# SCH_Custom_Arduino_2022-07-22.net
KiCad netlist of a schematic drawn in EasyEDA
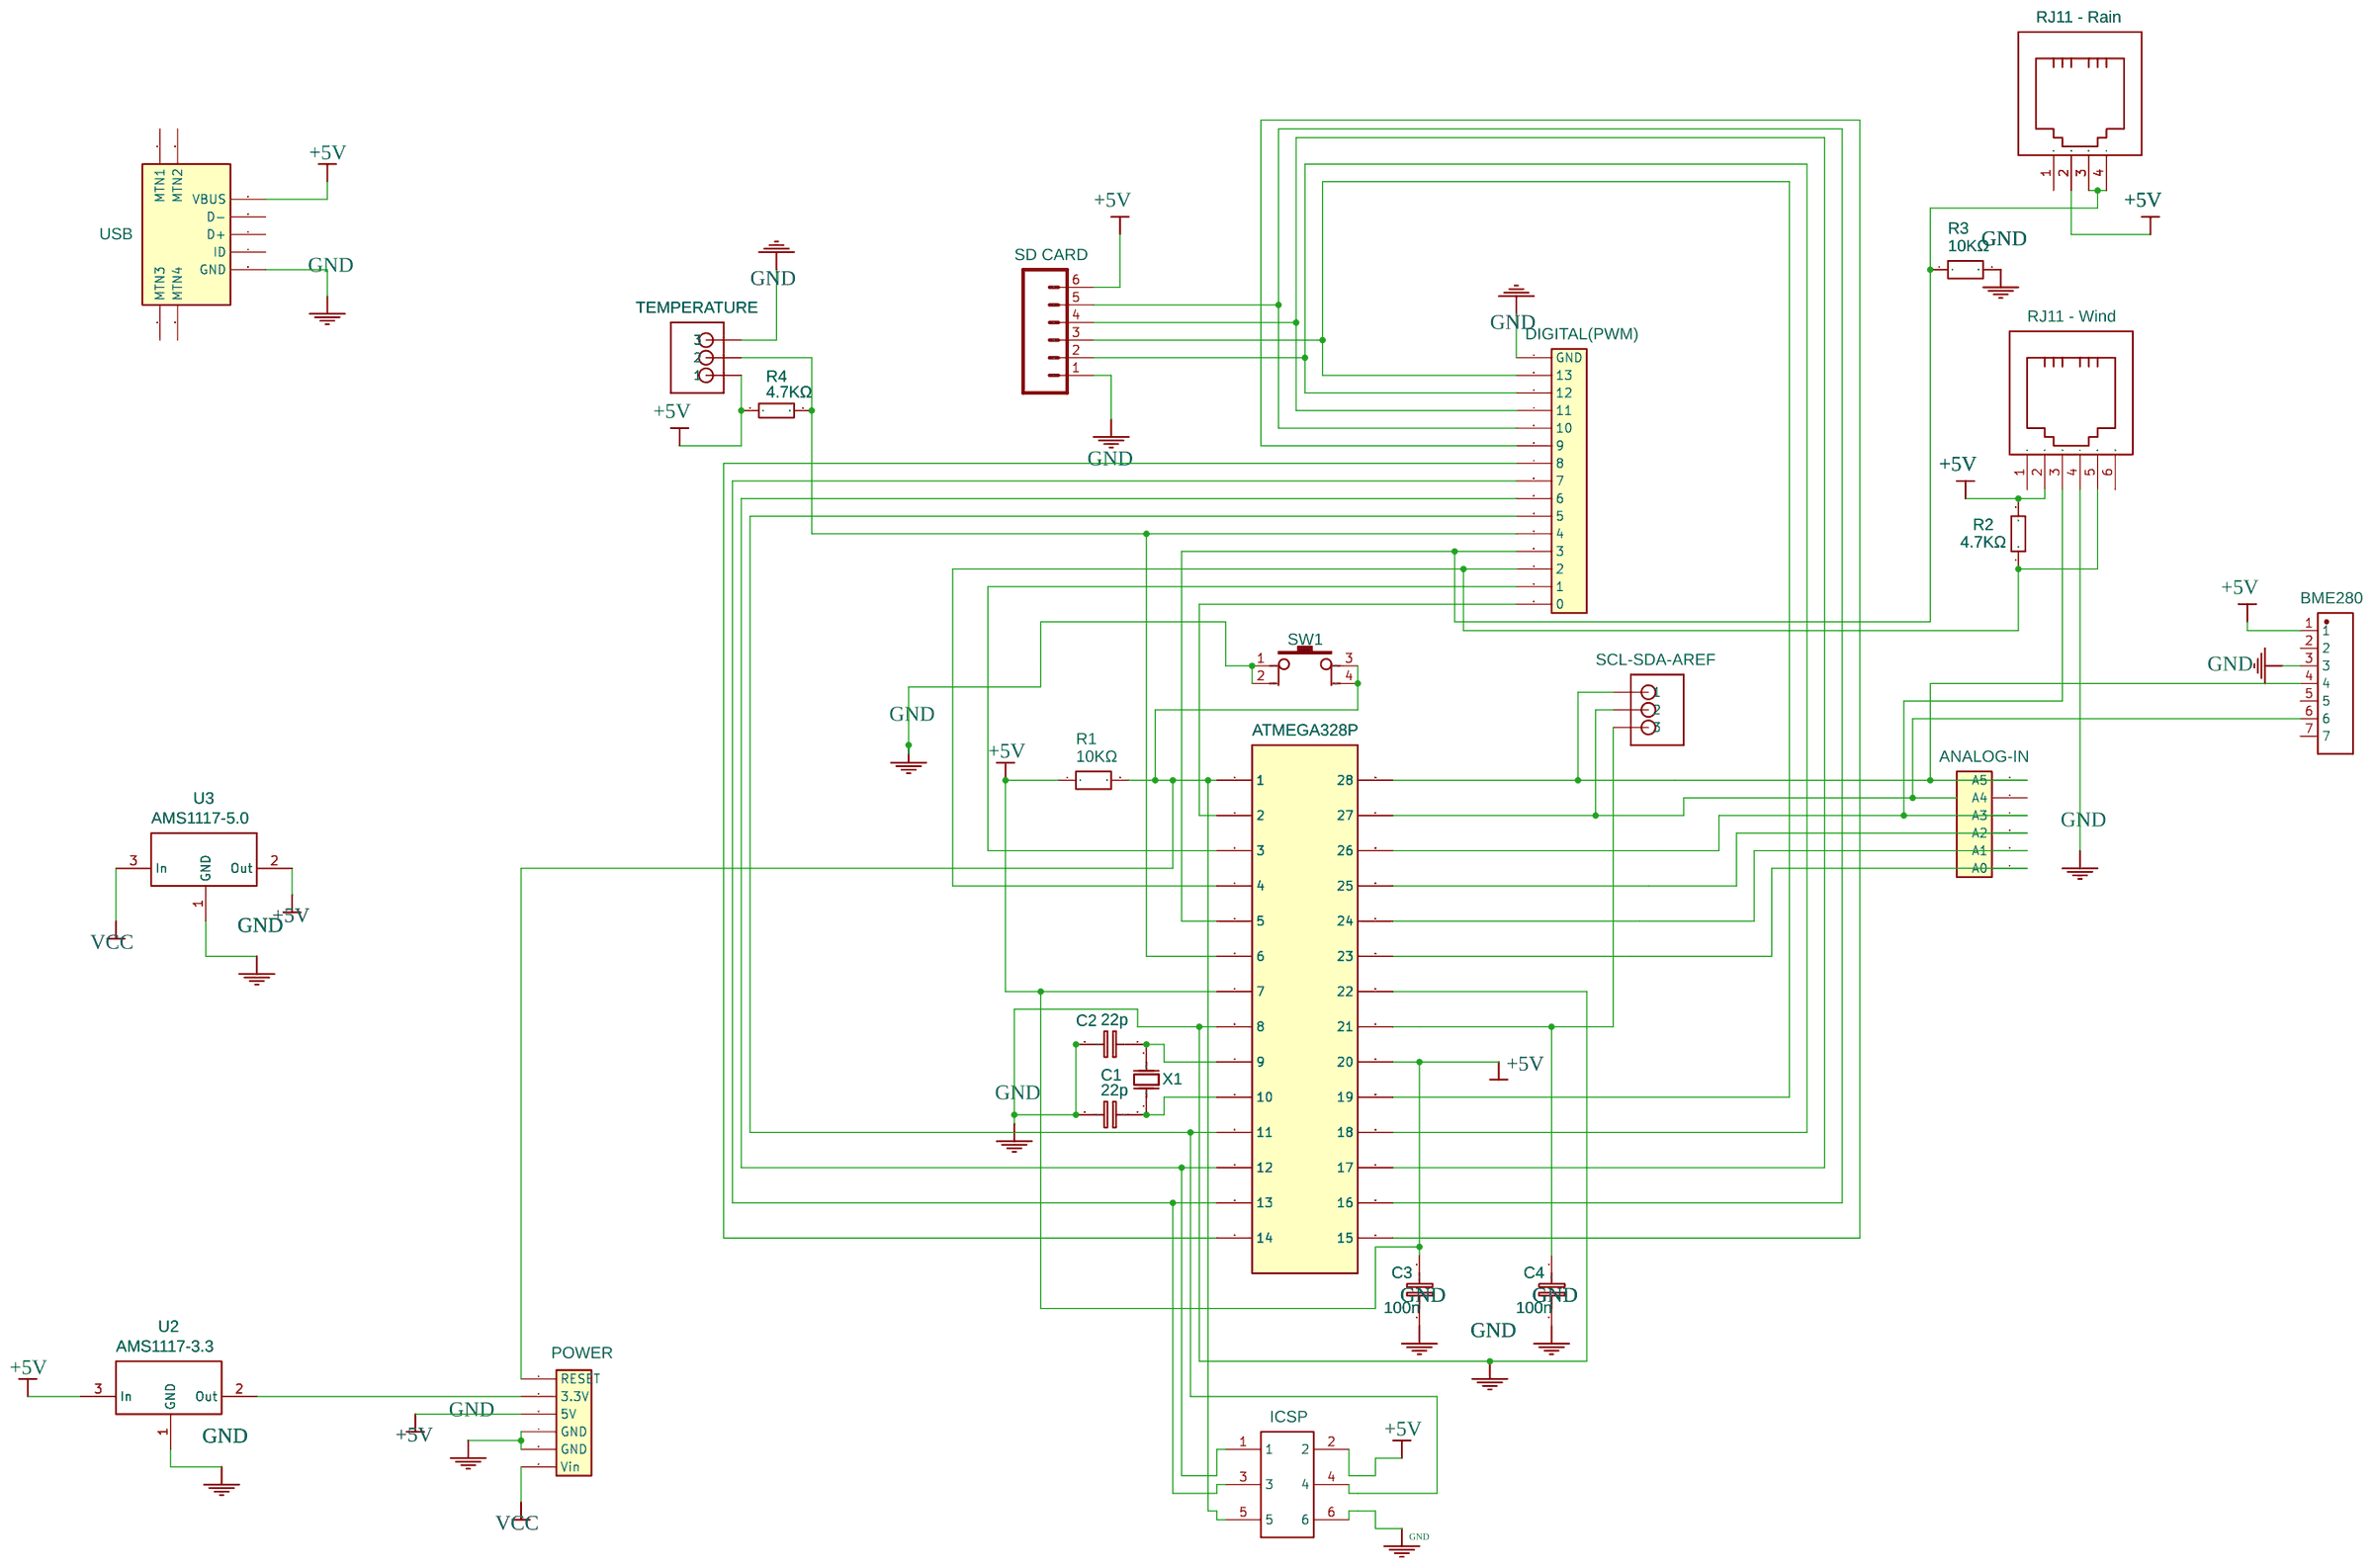
[diagram p0: schematic sheet]

(export (version "E")
  (design (tool "Eeschema 10.0.6"))
  (components
    (comp (ref "ANALOG-IN")
      (value "Header-Female-2.54_1x6")
      (fields (field (name "BOM_Supplier Part") "C40877"))
      (libsource (lib "") (part "Unknown_42720_21425"))
    )
    (comp (ref "ATMEGA328P")
      (value "DS1009-28AT1WX-0A2")
      (fields (field (name "BOM_Supplier Part") "C72121"))
      (libsource (lib "") (part "Unknown_42325_21530"))
    )
    (comp (ref "C1") (value "22p") (libsource (lib "") (part "Capacitor1_EU_1")))
    (comp (ref "C2") (value "22p") (libsource (lib "") (part "Capacitor1_EU_1")))
    (comp (ref "C3") (value "100n") (libsource (lib "") (part "Capacitor1_EU")))
    (comp (ref "C4") (value "100n") (libsource (lib "") (part "Capacitor1_EU")))
    (comp (ref "CN1")
      (value "BME280")
      (fields
        (field (name "BOM_Manufacturer Part") "1*7pin排间距2.54mm")
        (field (name "BOM_Supplier Part") "C9900012194")
      )
      (libsource (lib "") (part "1*7PIN排间距2.54MM"))
    )
    (comp (ref "DIGITAL(PWM)")
      (value "Header-Female-2.54_1x15")
      (fields
        (field (name "BOM_Manufacturer Part") "Female header1X15P 2.54mm")
        (field (name "BOM_Supplier Part") "C54104")
      )
      (libsource (lib "") (part "Unknown_42460_21230"))
    )
    (comp (ref "ICSP")
      (value "ICSP")
      (fields (field (name "BOM_Manufacturer Part") "2X3 PINHD"))
      (libsource (lib "") (part "2X3 PINHD"))
    )
    (comp (ref "POWER")
      (value "Header-Female-2.54_1x6")
      (fields (field (name "BOM_Supplier Part") "C40877"))
      (libsource (lib "") (part "Unknown_41895_21765"))
    )
    (comp (ref "R1")
      (value "10KΩ")
      (fields
        (field (name "BOM_Manufacturer Part") "RN1/2WS10KΩFT/BA1")
        (field (name "BOM_Supplier Part") "C385441")
      )
      (libsource (lib "") (part "10k"))
    )
    (comp (ref "R2")
      (value "4.7KΩ")
      (fields
        (field (name "BOM_Manufacturer Part") "MFR0W4F4701A50")
        (field (name "BOM_Supplier Part") "C57204")
      )
      (libsource (lib "") (part "4.7KΩ"))
    )
    (comp (ref "R3")
      (value "10KΩ")
      (fields
        (field (name "BOM_Manufacturer Part") "RN1/2WS10KΩFT/BA1")
        (field (name "BOM_Supplier Part") "C385441")
      )
      (libsource (lib "") (part "10k"))
    )
    (comp (ref "R4")
      (value "4.7KΩ")
      (fields
        (field (name "BOM_Manufacturer Part") "MFR0W4F4701A50")
        (field (name "BOM_Supplier Part") "C57204")
      )
      (libsource (lib "") (part "4.7KΩ_1"))
    )
    (comp (ref "RAIN")
      (value "RJ11 - Rain")
      (fields
        (field (name "BOM_Manufacturer Part") "FRJ11006-1100K6K20")
        (field (name "BOM_Supplier Part") "C456395")
      )
      (libsource (lib "") (part "FRJ11006-1100K6K20"))
    )
    (comp (ref "SCL-SDA-AREF") (value "SCL-SDA-AREF") (libsource (lib "") (part "JST-PH_3-PIN_HEADER")))
    (comp (ref "SD-CARD") (value "SD CARD") (libsource (lib "") (part "M063.5MM-6")))
    (comp (ref "SW1")
      (value "K2-1187SQ-A4SW")
      (fields (field (name "BOM_Supplier Part") "C92584"))
      (libsource (lib "") (part "Unknown_42325_21345"))
    )
    (comp (ref "TEMPERATURE") (value "TEMPERATURE") (libsource (lib "") (part "JST-PH_3-PIN_HEADER_1")))
    (comp (ref "U2")
      (value "AMS1117-3.3")
      (fields (field (name "BOM_Supplier Part") "C6186"))
      (libsource (lib "") (part "Unknown_41680_21750"))
    )
    (comp (ref "U3")
      (value "AMS1117-5.0")
      (fields (field (name "BOM_Supplier Part") "C6187"))
      (libsource (lib "") (part "Unknown_41700_21450"))
    )
    (comp (ref "USB1")
      (value "USB")
      (fields
        (field (name "BOM_Manufacturer Part") "MICRO USB 5S B")
        (field (name "BOM_Supplier Part") "C10418")
      )
      (libsource (lib "") (part "MICRO USB 5S B"))
    )
    (comp (ref "WIND")
      (value "RJ11 - Wind")
      (fields
        (field (name "BOM_Manufacturer Part") "FRJ11001-1100K6K20")
        (field (name "BOM_Supplier Part") "C456393")
      )
      (libsource (lib "") (part "FRJ11001-1100K6K20"))
    )
    (comp (ref "X1")
      (value "16MHZ")
      (fields
        (field (name "BOM_Manufacturer Part") "X49SD16MSD2SC")
        (field (name "BOM_Supplier Part") "C16212")
      )
      (libsource (lib "") (part "Unknown_42235_21570"))
    )
  )
  (nets
    (net (code "1") (name "+5V") (class "Default")
      (node (ref "ATMEGA328P") (pin "20") (pinfunction "20_20") (pintype "input"))
      (node (ref "ATMEGA328P") (pin "7") (pinfunction "7_7") (pintype "input"))
      (node (ref "C3") (pin "1") (pinfunction "1_1") (pintype "unspecified"))
      (node (ref "CN1") (pin "1") (pinfunction "1_1") (pintype "unspecified"))
      (node (ref "ICSP") (pin "2") (pinfunction "2_2") (pintype "unspecified"))
      (node (ref "POWER") (pin "3") (pinfunction "5V_3") (pintype "input"))
      (node (ref "R1") (pin "1") (pinfunction "1_1") (pintype "unspecified"))
      (node (ref "R2") (pin "2") (pinfunction "2_2") (pintype "input"))
      (node (ref "R4") (pin "1") (pinfunction "1_1") (pintype "input"))
      (node (ref "RAIN") (pin "2") (pinfunction "2_2") (pintype "unspecified"))
      (node (ref "SD-CARD") (pin "6") (pinfunction "6_6") (pintype "unspecified"))
      (node (ref "TEMPERATURE") (pin "P1") (pinfunction "1_P1") (pintype "unspecified"))
      (node (ref "U2") (pin "3") (pinfunction "In_3") (pintype "unspecified"))
      (node (ref "U3") (pin "2") (pinfunction "Out_2") (pintype "unspecified"))
      (node (ref "USB1") (pin "1") (pinfunction "VBUS_1") (pintype "input"))
      (node (ref "WIND") (pin "2") (pinfunction "2_2") (pintype "unspecified"))
    )
    (net (code "2") (name "GND") (class "Default")
      (node (ref "ATMEGA328P") (pin "22") (pinfunction "22_22") (pintype "input"))
      (node (ref "ATMEGA328P") (pin "8") (pinfunction "8_8") (pintype "input"))
      (node (ref "C1") (pin "1") (pinfunction "1_1") (pintype "unspecified"))
      (node (ref "C2") (pin "1") (pinfunction "1_1") (pintype "unspecified"))
      (node (ref "C3") (pin "2") (pinfunction "2_2") (pintype "unspecified"))
      (node (ref "C4") (pin "2") (pinfunction "2_2") (pintype "unspecified"))
      (node (ref "CN1") (pin "3") (pinfunction "3_3") (pintype "unspecified"))
      (node (ref "DIGITAL(PWM)") (pin "1") (pinfunction "GND_1") (pintype "input"))
      (node (ref "ICSP") (pin "6") (pinfunction "6_6") (pintype "unspecified"))
      (node (ref "POWER") (pin "4") (pinfunction "GND_4") (pintype "input"))
      (node (ref "POWER") (pin "5") (pinfunction "GND_5") (pintype "input"))
      (node (ref "R3") (pin "2") (pinfunction "2_2") (pintype "unspecified"))
      (node (ref "SD-CARD") (pin "1") (pinfunction "1_1") (pintype "unspecified"))
      (node (ref "SW1") (pin "1") (pinfunction "1_1") (pintype "input"))
      (node (ref "SW1") (pin "2") (pinfunction "2_2") (pintype "input"))
      (node (ref "TEMPERATURE") (pin "P3") (pinfunction "3_P3") (pintype "unspecified"))
      (node (ref "U2") (pin "1") (pinfunction "GND_1") (pintype "unspecified"))
      (node (ref "U3") (pin "1") (pinfunction "GND_1") (pintype "unspecified"))
      (node (ref "USB1") (pin "5") (pinfunction "GND_5") (pintype "input"))
      (node (ref "WIND") (pin "4") (pinfunction "4_4") (pintype "unspecified"))
    )
    (net (code "3") (name "Net-(ANALOG-IN-A0)") (class "Default")
      (node (ref "ANALOG-IN") (pin "1") (pinfunction "A0_1") (pintype "input"))
      (node (ref "ATMEGA328P") (pin "23") (pinfunction "23_23") (pintype "input"))
    )
    (net (code "4") (name "Net-(ANALOG-IN-A1)") (class "Default")
      (node (ref "ANALOG-IN") (pin "2") (pinfunction "A1_2") (pintype "input"))
      (node (ref "ATMEGA328P") (pin "24") (pinfunction "24_24") (pintype "input"))
    )
    (net (code "5") (name "Net-(ANALOG-IN-A2)") (class "Default")
      (node (ref "ANALOG-IN") (pin "3") (pinfunction "A2_3") (pintype "input"))
      (node (ref "ATMEGA328P") (pin "25") (pinfunction "25_25") (pintype "input"))
    )
    (net (code "6") (name "Net-(ANALOG-IN-A3)") (class "Default")
      (node (ref "ANALOG-IN") (pin "4") (pinfunction "A3_4") (pintype "input"))
      (node (ref "ATMEGA328P") (pin "26") (pinfunction "26_26") (pintype "input"))
      (node (ref "WIND") (pin "3") (pinfunction "3_3") (pintype "unspecified"))
    )
    (net (code "7") (name "Net-(ANALOG-IN-A5)") (class "Default")
      (node (ref "ANALOG-IN") (pin "6") (pinfunction "A5_6") (pintype "input"))
      (node (ref "ATMEGA328P") (pin "28") (pinfunction "28_28") (pintype "input"))
      (node (ref "CN1") (pin "4") (pinfunction "4_4") (pintype "unspecified"))
      (node (ref "SCL-SDA-AREF") (pin "P1") (pinfunction "1_P1") (pintype "unspecified"))
    )
    (net (code "8") (name "Net-(DIGITAL(PWM)-0)") (class "Default")
      (node (ref "ATMEGA328P") (pin "2") (pinfunction "2_2") (pintype "input"))
      (node (ref "DIGITAL(PWM)") (pin "15") (pinfunction "0_15") (pintype "input"))
    )
    (net (code "9") (name "Net-(DIGITAL(PWM)-1)") (class "Default")
      (node (ref "ATMEGA328P") (pin "3") (pinfunction "3_3") (pintype "input"))
      (node (ref "DIGITAL(PWM)") (pin "14") (pinfunction "1_14") (pintype "input"))
    )
    (net (code "10") (name "Net-(DIGITAL(PWM)-2)") (class "Default")
      (node (ref "ATMEGA328P") (pin "4") (pinfunction "4_4") (pintype "input"))
      (node (ref "DIGITAL(PWM)") (pin "13") (pinfunction "2_13") (pintype "input"))
      (node (ref "R2") (pin "1") (pinfunction "1_1") (pintype "input"))
      (node (ref "WIND") (pin "5") (pinfunction "5_5") (pintype "unspecified"))
    )
    (net (code "11") (name "Net-(DIGITAL(PWM)-3)") (class "Default")
      (node (ref "ATMEGA328P") (pin "5") (pinfunction "5_5") (pintype "input"))
      (node (ref "DIGITAL(PWM)") (pin "12") (pinfunction "3_12") (pintype "input"))
      (node (ref "R3") (pin "1") (pinfunction "1_1") (pintype "unspecified"))
      (node (ref "RAIN") (pin "3") (pinfunction "3_3") (pintype "unspecified"))
      (node (ref "RAIN") (pin "4") (pinfunction "4_4") (pintype "unspecified"))
    )
    (net (code "12") (name "Net-(DIGITAL(PWM)-4)") (class "Default")
      (node (ref "ATMEGA328P") (pin "6") (pinfunction "6_6") (pintype "input"))
      (node (ref "DIGITAL(PWM)") (pin "11") (pinfunction "4_11") (pintype "input"))
      (node (ref "R4") (pin "2") (pinfunction "2_2") (pintype "input"))
      (node (ref "TEMPERATURE") (pin "P2") (pinfunction "2_P2") (pintype "unspecified"))
    )
    (net (code "13") (name "Net-(DIGITAL(PWM)-5)") (class "Default")
      (node (ref "ATMEGA328P") (pin "11") (pinfunction "11_11") (pintype "input"))
      (node (ref "DIGITAL(PWM)") (pin "10") (pinfunction "5_10") (pintype "input"))
      (node (ref "ICSP") (pin "4") (pinfunction "4_4") (pintype "unspecified"))
    )
    (net (code "14") (name "Net-(DIGITAL(PWM)-6)") (class "Default")
      (node (ref "ATMEGA328P") (pin "12") (pinfunction "12_12") (pintype "input"))
      (node (ref "DIGITAL(PWM)") (pin "9") (pinfunction "6_9") (pintype "input"))
      (node (ref "ICSP") (pin "1") (pinfunction "1_1") (pintype "unspecified"))
    )
    (net (code "15") (name "Net-(DIGITAL(PWM)-7)") (class "Default")
      (node (ref "ATMEGA328P") (pin "13") (pinfunction "13_13") (pintype "input"))
      (node (ref "DIGITAL(PWM)") (pin "8") (pinfunction "7_8") (pintype "input"))
      (node (ref "ICSP") (pin "3") (pinfunction "3_3") (pintype "unspecified"))
    )
    (net (code "16") (name "Net-(DIGITAL(PWM)-8)") (class "Default")
      (node (ref "ATMEGA328P") (pin "14") (pinfunction "14_14") (pintype "input"))
      (node (ref "DIGITAL(PWM)") (pin "7") (pinfunction "8_7") (pintype "input"))
    )
    (net (code "17") (name "Net-(DIGITAL(PWM)-9)") (class "Default")
      (node (ref "ATMEGA328P") (pin "15") (pinfunction "15_15") (pintype "input"))
      (node (ref "DIGITAL(PWM)") (pin "6") (pinfunction "9_6") (pintype "input"))
    )
    (net (code "18") (name "Net-(DIGITAL(PWM)-10)") (class "Default")
      (node (ref "ATMEGA328P") (pin "16") (pinfunction "16_16") (pintype "input"))
      (node (ref "DIGITAL(PWM)") (pin "5") (pinfunction "10_5") (pintype "input"))
      (node (ref "SD-CARD") (pin "5") (pinfunction "5_5") (pintype "unspecified"))
    )
    (net (code "19") (name "Net-(DIGITAL(PWM)-11)") (class "Default")
      (node (ref "ATMEGA328P") (pin "17") (pinfunction "17_17") (pintype "input"))
      (node (ref "DIGITAL(PWM)") (pin "4") (pinfunction "11_4") (pintype "input"))
      (node (ref "SD-CARD") (pin "4") (pinfunction "4_4") (pintype "unspecified"))
    )
    (net (code "20") (name "Net-(DIGITAL(PWM)-12)") (class "Default")
      (node (ref "ATMEGA328P") (pin "18") (pinfunction "18_18") (pintype "input"))
      (node (ref "DIGITAL(PWM)") (pin "3") (pinfunction "12_3") (pintype "input"))
      (node (ref "SD-CARD") (pin "2") (pinfunction "2_2") (pintype "unspecified"))
    )
    (net (code "21") (name "Net-(DIGITAL(PWM)-13)") (class "Default")
      (node (ref "ATMEGA328P") (pin "19") (pinfunction "19_19") (pintype "input"))
      (node (ref "DIGITAL(PWM)") (pin "2") (pinfunction "13_2") (pintype "input"))
      (node (ref "SD-CARD") (pin "3") (pinfunction "3_3") (pintype "unspecified"))
    )
    (net (code "22") (name "Net-(POWER-3.3V)") (class "Default")
      (node (ref "POWER") (pin "2") (pinfunction "3.3V_2") (pintype "input"))
      (node (ref "U2") (pin "2") (pinfunction "Out_2") (pintype "unspecified"))
    )
    (net (code "23") (name "Net-(POWER-RESET)") (class "Default")
      (node (ref "ATMEGA328P") (pin "1") (pinfunction "1_1") (pintype "input"))
      (node (ref "ICSP") (pin "5") (pinfunction "5_5") (pintype "unspecified"))
      (node (ref "POWER") (pin "1") (pinfunction "RESET_1") (pintype "input"))
      (node (ref "R1") (pin "2") (pinfunction "2_2") (pintype "unspecified"))
      (node (ref "SW1") (pin "3") (pinfunction "3_3") (pintype "input"))
      (node (ref "SW1") (pin "4") (pinfunction "4_4") (pintype "input"))
    )
    (net (code "24") (name "Net-(SCL-SDA-AREF-2)") (class "Default")
      (node (ref "ATMEGA328P") (pin "27") (pinfunction "27_27") (pintype "input"))
      (node (ref "CN1") (pin "6") (pinfunction "6_6") (pintype "unspecified"))
      (node (ref "SCL-SDA-AREF") (pin "P2") (pinfunction "2_P2") (pintype "unspecified"))
    )
    (net (code "25") (name "Net-(SCL-SDA-AREF-3)") (class "Default")
      (node (ref "ATMEGA328P") (pin "21") (pinfunction "21_21") (pintype "input"))
      (node (ref "C4") (pin "1") (pinfunction "1_1") (pintype "unspecified"))
      (node (ref "SCL-SDA-AREF") (pin "P3") (pinfunction "3_P3") (pintype "unspecified"))
    )
    (net (code "26") (name "Net-(X1-OSC1)") (class "Default")
      (node (ref "ATMEGA328P") (pin "10") (pinfunction "10_10") (pintype "input"))
      (node (ref "C1") (pin "2") (pinfunction "2_2") (pintype "unspecified"))
      (node (ref "X1") (pin "1") (pinfunction "OSC1_1") (pintype "input"))
    )
    (net (code "27") (name "Net-(X1-OSC2)") (class "Default")
      (node (ref "ATMEGA328P") (pin "9") (pinfunction "9_9") (pintype "input"))
      (node (ref "C2") (pin "2") (pinfunction "2_2") (pintype "unspecified"))
      (node (ref "X1") (pin "2") (pinfunction "OSC2_2") (pintype "input"))
    )
    (net (code "28") (name "VCC") (class "Default")
      (node (ref "POWER") (pin "6") (pinfunction "Vin_6") (pintype "input"))
      (node (ref "U3") (pin "3") (pinfunction "In_3") (pintype "unspecified"))
    )
    (net (code "29") (name "unconnected-(ANALOG-IN-A4-Pad5)") (class "Default")
      (node (ref "ANALOG-IN") (pin "5") (pinfunction "A4_5") (pintype "input"))
    )
    (net (code "30") (name "unconnected-(CN1-Pad2)") (class "Default")
      (node (ref "CN1") (pin "2") (pinfunction "2_2") (pintype "unspecified"))
    )
    (net (code "31") (name "unconnected-(CN1-Pad5)") (class "Default")
      (node (ref "CN1") (pin "5") (pinfunction "5_5") (pintype "unspecified"))
    )
    (net (code "32") (name "unconnected-(CN1-Pad7)") (class "Default")
      (node (ref "CN1") (pin "7") (pinfunction "7_7") (pintype "unspecified"))
    )
    (net (code "33") (name "unconnected-(RAIN-Pad1)") (class "Default")
      (node (ref "RAIN") (pin "1") (pinfunction "1_1") (pintype "unspecified"))
    )
    (net (code "34") (name "unconnected-(USB1-D+-Pad3)") (class "Default")
      (node (ref "USB1") (pin "3") (pinfunction "D+_3") (pintype "input"))
    )
    (net (code "35") (name "unconnected-(USB1-D--Pad2)") (class "Default")
      (node (ref "USB1") (pin "2") (pinfunction "D-_2") (pintype "input"))
    )
    (net (code "36") (name "unconnected-(USB1-ID-Pad4)") (class "Default")
      (node (ref "USB1") (pin "4") (pinfunction "ID_4") (pintype "input"))
    )
    (net (code "37") (name "unconnected-(USB1-MTN1-Pad0)") (class "Default")
      (node (ref "USB1") (pin "0") (pinfunction "MTN1_0") (pintype "input"))
    )
    (net (code "38") (name "unconnected-(USB1-MTN2-Pad0)") (class "Default")
      (node (ref "USB1") (pin "0") (pinfunction "MTN2_0") (pintype "input"))
    )
    (net (code "39") (name "unconnected-(USB1-MTN3-Pad0)") (class "Default")
      (node (ref "USB1") (pin "0") (pinfunction "MTN3_0") (pintype "input"))
    )
    (net (code "40") (name "unconnected-(USB1-MTN4-Pad0)") (class "Default")
      (node (ref "USB1") (pin "0") (pinfunction "MTN4_0") (pintype "input"))
    )
    (net (code "41") (name "unconnected-(WIND-Pad1)") (class "Default")
      (node (ref "WIND") (pin "1") (pinfunction "1_1") (pintype "unspecified"))
    )
    (net (code "42") (name "unconnected-(WIND-Pad6)") (class "Default")
      (node (ref "WIND") (pin "6") (pinfunction "6_6") (pintype "unspecified"))
    )
  )
)
